# stm32.net
KiCad netlist of a schematic drawn in Altium Designer
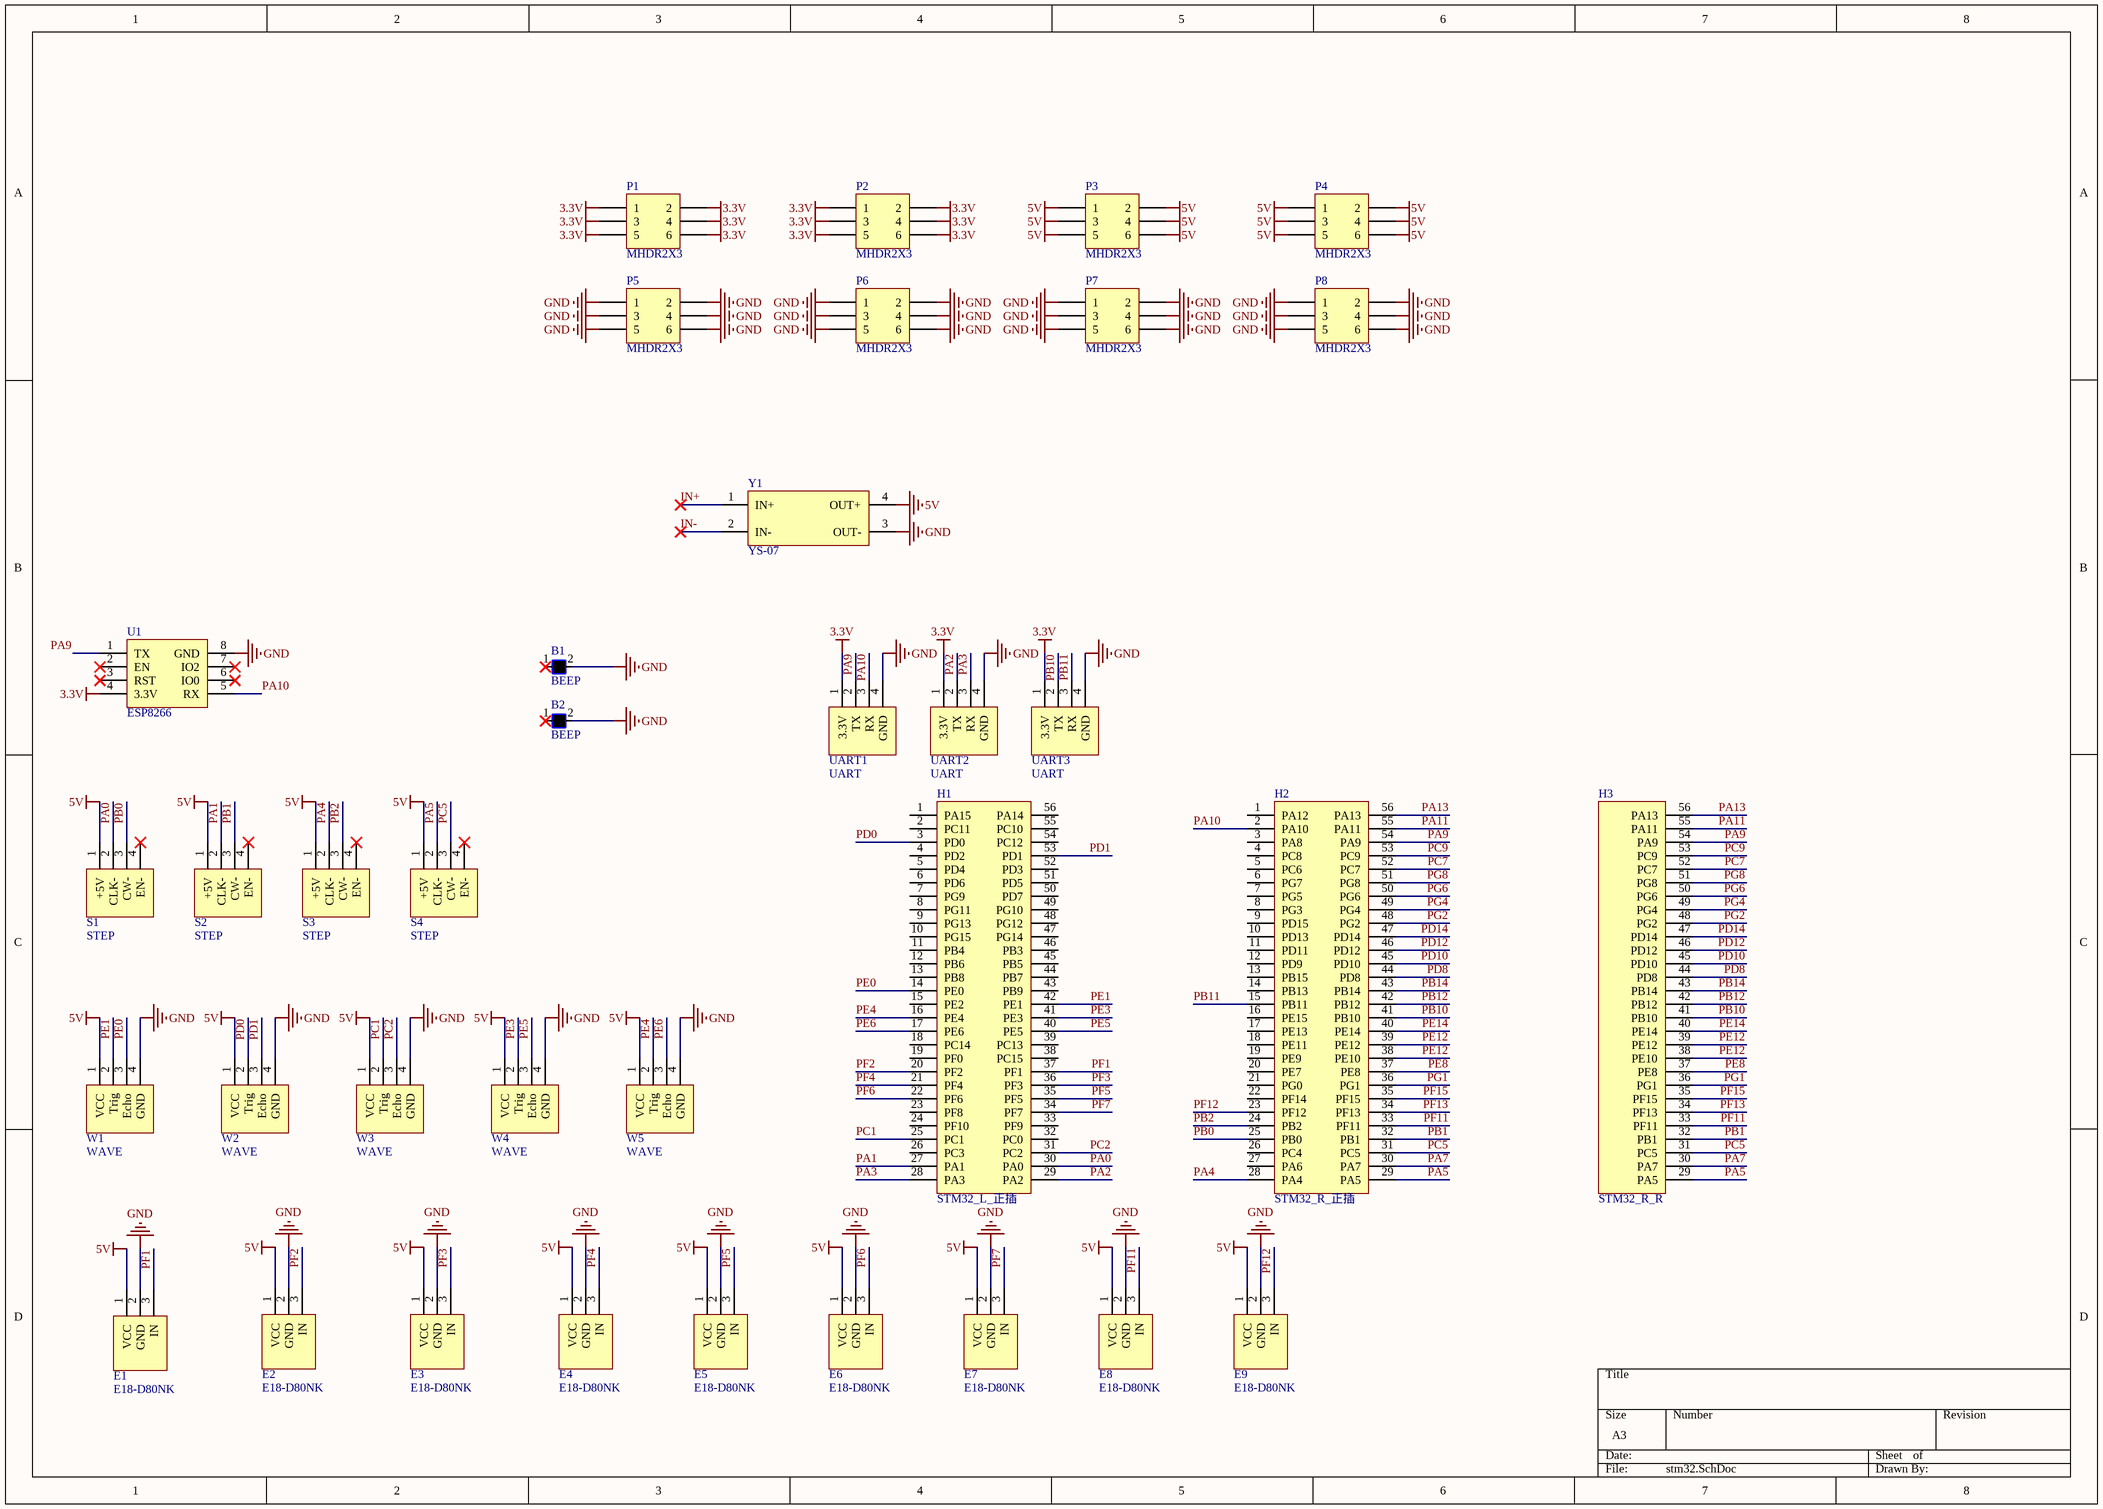
[diagram p0: stm32.SchDoc]

(export (version "E")
  (design (tool "Eeschema 10.0.6"))
  (components
    (comp (ref "B1") (value "BEEP") (footprint "BEEP") (libsource (lib "stm32") (part "BEEP")))
    (comp (ref "B2") (value "BEEP") (footprint "BEEP") (libsource (lib "stm32") (part "BEEP")))
    (comp (ref "E1") (value "E18-D80NK") (footprint "E18") (libsource (lib "stm32") (part "E18-D80NK")))
    (comp (ref "E2") (value "E18-D80NK") (footprint "E18") (libsource (lib "stm32") (part "E18-D80NK")))
    (comp (ref "E3") (value "E18-D80NK") (footprint "E18") (libsource (lib "stm32") (part "E18-D80NK")))
    (comp (ref "E4") (value "E18-D80NK") (footprint "E18") (libsource (lib "stm32") (part "E18-D80NK")))
    (comp (ref "E5") (value "E18-D80NK") (footprint "E18") (libsource (lib "stm32") (part "E18-D80NK")))
    (comp (ref "E6") (value "E18-D80NK") (footprint "E18") (libsource (lib "stm32") (part "E18-D80NK")))
    (comp (ref "E7") (value "E18-D80NK") (footprint "E18") (libsource (lib "stm32") (part "E18-D80NK")))
    (comp (ref "E8") (value "E18-D80NK") (footprint "E18") (libsource (lib "stm32") (part "E18-D80NK")))
    (comp (ref "E9") (value "E18-D80NK") (footprint "E18") (libsource (lib "stm32") (part "E18-D80NK")))
    (comp (ref "H1")
      (value "STM32_L_正插")
      (footprint "Header2*28")
      (libsource (lib "stm32") (part "STM32_L_正插"))
    )
    (comp (ref "H2")
      (value "STM32_R_正插")
      (footprint "Header2*28")
      (libsource (lib "stm32") (part "STM32_R_正插"))
    )
    (comp (ref "H3")
      (value "STM32_R_R")
      (footprint "HEADER1*28")
      (libsource (lib "stm32") (part "STM32_R_R"))
    )
    (comp (ref "P1")
      (value "MHDR2X3")
      (footprint "MHDR2X3")
      (description "Header, 3-Pin, Dual row")
      (fields (field (name "PUBLISHER") "Altium Limited"))
      (libsource (lib "Miscellaneous Connectors") (part "MHDR2X3"))
    )
    (comp (ref "P2")
      (value "MHDR2X3")
      (footprint "MHDR2X3")
      (description "Header, 3-Pin, Dual row")
      (fields (field (name "PUBLISHER") "Altium Limited"))
      (libsource (lib "Miscellaneous Connectors") (part "MHDR2X3"))
    )
    (comp (ref "P3")
      (value "MHDR2X3")
      (footprint "MHDR2X3")
      (description "Header, 3-Pin, Dual row")
      (fields (field (name "PUBLISHER") "Altium Limited"))
      (libsource (lib "Miscellaneous Connectors") (part "MHDR2X3"))
    )
    (comp (ref "P4")
      (value "MHDR2X3")
      (footprint "MHDR2X3")
      (description "Header, 3-Pin, Dual row")
      (fields (field (name "PUBLISHER") "Altium Limited"))
      (libsource (lib "Miscellaneous Connectors") (part "MHDR2X3"))
    )
    (comp (ref "P5")
      (value "MHDR2X3")
      (footprint "MHDR2X3")
      (description "Header, 3-Pin, Dual row")
      (fields (field (name "PUBLISHER") "Altium Limited"))
      (libsource (lib "Miscellaneous Connectors") (part "MHDR2X3"))
    )
    (comp (ref "P6")
      (value "MHDR2X3")
      (footprint "MHDR2X3")
      (description "Header, 3-Pin, Dual row")
      (fields (field (name "PUBLISHER") "Altium Limited"))
      (libsource (lib "Miscellaneous Connectors") (part "MHDR2X3"))
    )
    (comp (ref "P7")
      (value "MHDR2X3")
      (footprint "MHDR2X3")
      (description "Header, 3-Pin, Dual row")
      (fields (field (name "PUBLISHER") "Altium Limited"))
      (libsource (lib "Miscellaneous Connectors") (part "MHDR2X3"))
    )
    (comp (ref "P8")
      (value "MHDR2X3")
      (footprint "MHDR2X3")
      (description "Header, 3-Pin, Dual row")
      (fields (field (name "PUBLISHER") "Altium Limited"))
      (libsource (lib "Miscellaneous Connectors") (part "MHDR2X3"))
    )
    (comp (ref "S1") (value "STEP") (footprint "STEP") (libsource (lib "stm32") (part "STEP")))
    (comp (ref "S2") (value "STEP") (footprint "STEP") (libsource (lib "stm32") (part "STEP")))
    (comp (ref "S3") (value "STEP") (footprint "STEP") (libsource (lib "stm32") (part "STEP")))
    (comp (ref "S4") (value "STEP") (footprint "STEP") (libsource (lib "stm32") (part "STEP")))
    (comp (ref "U1") (value "ESP8266") (footprint "ESP8266") (libsource (lib "stm32") (part "ESP8266")))
    (comp (ref "UART1") (value "UART") (footprint "UART") (libsource (lib "stm32") (part "UART")))
    (comp (ref "UART2") (value "UART") (footprint "UART") (libsource (lib "stm32") (part "UART")))
    (comp (ref "UART3") (value "UART") (footprint "UART") (libsource (lib "stm32") (part "UART")))
    (comp (ref "W1") (value "WAVE") (footprint "WAVE1*4") (libsource (lib "stm32") (part "WAVE")))
    (comp (ref "W2") (value "WAVE") (footprint "WAVE1*4") (libsource (lib "stm32") (part "WAVE")))
    (comp (ref "W3") (value "WAVE") (footprint "WAVE1*4") (libsource (lib "stm32") (part "WAVE")))
    (comp (ref "W4") (value "WAVE") (footprint "WAVE1*4") (libsource (lib "stm32") (part "WAVE")))
    (comp (ref "W5") (value "WAVE") (footprint "WAVE1*4") (libsource (lib "stm32") (part "WAVE")))
    (comp (ref "Y1") (value "YS-07") (footprint "YS-07") (libsource (lib "stm32") (part "YS-07")))
  )
  (nets
    (net (code "1") (name "/IN+") (class "Default")
      (node (ref "Y1") (pin "1") (pinfunction "IN+_1") (pintype "passive+no_connect"))
    )
    (net (code "2") (name "/IN-") (class "Default")
      (node (ref "Y1") (pin "2") (pinfunction "IN-_2") (pintype "passive+no_connect"))
    )
    (net (code "3") (name "/PA0") (class "Default")
      (node (ref "H1") (pin "30") (pinfunction "PA0_30") (pintype "passive"))
      (node (ref "S1") (pin "2") (pinfunction "CLK-_2") (pintype "passive"))
    )
    (net (code "4") (name "/PA1") (class "Default")
      (node (ref "H1") (pin "27") (pinfunction "PA1_27") (pintype "passive"))
      (node (ref "S2") (pin "2") (pinfunction "CLK-_2") (pintype "passive"))
    )
    (net (code "5") (name "/PA2") (class "Default")
      (node (ref "H1") (pin "29") (pinfunction "PA2_29") (pintype "passive"))
      (node (ref "UART2") (pin "2") (pinfunction "TX_2") (pintype "passive"))
    )
    (net (code "6") (name "/PA3") (class "Default")
      (node (ref "H1") (pin "28") (pinfunction "PA3_28") (pintype "passive"))
      (node (ref "UART2") (pin "3") (pinfunction "RX_3") (pintype "passive"))
    )
    (net (code "7") (name "/PA4") (class "Default")
      (node (ref "H2") (pin "28") (pinfunction "PA4_28") (pintype "passive"))
      (node (ref "S3") (pin "2") (pinfunction "CLK-_2") (pintype "passive"))
    )
    (net (code "8") (name "/PA5") (class "Default")
      (node (ref "H2") (pin "29") (pinfunction "PA5_29") (pintype "passive"))
      (node (ref "H3") (pin "29") (pinfunction "PA5_29") (pintype "passive"))
      (node (ref "S4") (pin "2") (pinfunction "CLK-_2") (pintype "passive"))
    )
    (net (code "9") (name "/PA7") (class "Default")
      (node (ref "H2") (pin "30") (pinfunction "PA7_30") (pintype "passive"))
      (node (ref "H3") (pin "30") (pinfunction "PA7_30") (pintype "passive"))
    )
    (net (code "10") (name "/PA9") (class "Default")
      (node (ref "H2") (pin "54") (pinfunction "PA9_54") (pintype "passive"))
      (node (ref "H3") (pin "54") (pinfunction "PA9_54") (pintype "passive"))
      (node (ref "U1") (pin "1") (pinfunction "TX_1") (pintype "passive"))
      (node (ref "UART1") (pin "2") (pinfunction "TX_2") (pintype "passive"))
    )
    (net (code "11") (name "/PA10") (class "Default")
      (node (ref "H2") (pin "2") (pinfunction "PA10_2") (pintype "passive"))
      (node (ref "U1") (pin "5") (pinfunction "RX_5") (pintype "passive"))
      (node (ref "UART1") (pin "3") (pinfunction "RX_3") (pintype "passive"))
    )
    (net (code "12") (name "/PA11") (class "Default")
      (node (ref "H2") (pin "55") (pinfunction "PA11_55") (pintype "passive"))
      (node (ref "H3") (pin "55") (pinfunction "PA11_55") (pintype "passive"))
    )
    (net (code "13") (name "/PA13") (class "Default")
      (node (ref "H2") (pin "56") (pinfunction "PA13_56") (pintype "passive"))
      (node (ref "H3") (pin "56") (pinfunction "PA13_56") (pintype "passive"))
    )
    (net (code "14") (name "/PB0") (class "Default")
      (node (ref "H2") (pin "25") (pinfunction "PB0_25") (pintype "passive"))
      (node (ref "S1") (pin "3") (pinfunction "CW-_3") (pintype "passive"))
    )
    (net (code "15") (name "/PB1") (class "Default")
      (node (ref "H2") (pin "32") (pinfunction "PB1_32") (pintype "passive"))
      (node (ref "H3") (pin "32") (pinfunction "PB1_32") (pintype "passive"))
      (node (ref "S2") (pin "3") (pinfunction "CW-_3") (pintype "passive"))
    )
    (net (code "16") (name "/PB2") (class "Default")
      (node (ref "H2") (pin "24") (pinfunction "PB2_24") (pintype "passive"))
      (node (ref "S3") (pin "3") (pinfunction "CW-_3") (pintype "passive"))
    )
    (net (code "17") (name "/PB10") (class "Default")
      (node (ref "H2") (pin "41") (pinfunction "PB10_41") (pintype "passive"))
      (node (ref "H3") (pin "41") (pinfunction "PB10_41") (pintype "passive"))
      (node (ref "UART3") (pin "2") (pinfunction "TX_2") (pintype "passive"))
    )
    (net (code "18") (name "/PB11") (class "Default")
      (node (ref "H2") (pin "15") (pinfunction "PB11_15") (pintype "passive"))
      (node (ref "UART3") (pin "3") (pinfunction "RX_3") (pintype "passive"))
    )
    (net (code "19") (name "/PB12") (class "Default")
      (node (ref "H2") (pin "42") (pinfunction "PB12_42") (pintype "passive"))
      (node (ref "H3") (pin "42") (pinfunction "PB12_42") (pintype "passive"))
    )
    (net (code "20") (name "/PB14") (class "Default")
      (node (ref "H2") (pin "43") (pinfunction "PB14_43") (pintype "passive"))
      (node (ref "H3") (pin "43") (pinfunction "PB14_43") (pintype "passive"))
    )
    (net (code "21") (name "/PC1") (class "Default")
      (node (ref "H1") (pin "25") (pinfunction "PC1_25") (pintype "passive"))
      (node (ref "W3") (pin "2") (pinfunction "Trig_2") (pintype "passive"))
    )
    (net (code "22") (name "/PC2") (class "Default")
      (node (ref "H1") (pin "31") (pinfunction "PC2_31") (pintype "passive"))
      (node (ref "W3") (pin "3") (pinfunction "Echo_3") (pintype "passive"))
    )
    (net (code "23") (name "/PC5") (class "Default")
      (node (ref "H2") (pin "31") (pinfunction "PC5_31") (pintype "passive"))
      (node (ref "H3") (pin "31") (pinfunction "PC5_31") (pintype "passive"))
      (node (ref "S4") (pin "3") (pinfunction "CW-_3") (pintype "passive"))
    )
    (net (code "24") (name "/PC7") (class "Default")
      (node (ref "H2") (pin "52") (pinfunction "PC7_52") (pintype "passive"))
      (node (ref "H3") (pin "52") (pinfunction "PC7_52") (pintype "passive"))
    )
    (net (code "25") (name "/PC9") (class "Default")
      (node (ref "H2") (pin "53") (pinfunction "PC9_53") (pintype "passive"))
      (node (ref "H3") (pin "53") (pinfunction "PC9_53") (pintype "passive"))
    )
    (net (code "26") (name "/PD0") (class "Default")
      (node (ref "H1") (pin "3") (pinfunction "PD0_3") (pintype "passive"))
      (node (ref "W2") (pin "2") (pinfunction "Trig_2") (pintype "passive"))
    )
    (net (code "27") (name "/PD1") (class "Default")
      (node (ref "H1") (pin "53") (pinfunction "PD1_53") (pintype "passive"))
      (node (ref "W2") (pin "3") (pinfunction "Echo_3") (pintype "passive"))
    )
    (net (code "28") (name "/PD8") (class "Default")
      (node (ref "H2") (pin "44") (pinfunction "PD8_44") (pintype "passive"))
      (node (ref "H3") (pin "44") (pinfunction "PD8_44") (pintype "passive"))
    )
    (net (code "29") (name "/PD10") (class "Default")
      (node (ref "H2") (pin "45") (pinfunction "PD10_45") (pintype "passive"))
      (node (ref "H3") (pin "45") (pinfunction "PD10_45") (pintype "passive"))
    )
    (net (code "30") (name "/PD12") (class "Default")
      (node (ref "H2") (pin "46") (pinfunction "PD12_46") (pintype "passive"))
      (node (ref "H3") (pin "46") (pinfunction "PD12_46") (pintype "passive"))
    )
    (net (code "31") (name "/PD14") (class "Default")
      (node (ref "H2") (pin "47") (pinfunction "PD14_47") (pintype "passive"))
      (node (ref "H3") (pin "47") (pinfunction "PD14_47") (pintype "passive"))
    )
    (net (code "32") (name "/PE0") (class "Default")
      (node (ref "H1") (pin "14") (pinfunction "PE0_14") (pintype "passive"))
      (node (ref "W1") (pin "3") (pinfunction "Echo_3") (pintype "passive"))
    )
    (net (code "33") (name "/PE1") (class "Default")
      (node (ref "H1") (pin "42") (pinfunction "PE1_42") (pintype "passive"))
      (node (ref "W1") (pin "2") (pinfunction "Trig_2") (pintype "passive"))
    )
    (net (code "34") (name "/PE3") (class "Default")
      (node (ref "H1") (pin "41") (pinfunction "PE3_41") (pintype "passive"))
      (node (ref "W4") (pin "2") (pinfunction "Trig_2") (pintype "passive"))
    )
    (net (code "35") (name "/PE4") (class "Default")
      (node (ref "H1") (pin "16") (pinfunction "PE4_16") (pintype "passive"))
      (node (ref "W5") (pin "2") (pinfunction "Trig_2") (pintype "passive"))
    )
    (net (code "36") (name "/PE5") (class "Default")
      (node (ref "H1") (pin "40") (pinfunction "PE5_40") (pintype "passive"))
      (node (ref "W4") (pin "3") (pinfunction "Echo_3") (pintype "passive"))
    )
    (net (code "37") (name "/PE6") (class "Default")
      (node (ref "H1") (pin "17") (pinfunction "PE6_17") (pintype "passive"))
      (node (ref "W5") (pin "3") (pinfunction "Echo_3") (pintype "passive"))
    )
    (net (code "38") (name "/PE8") (class "Default")
      (node (ref "H2") (pin "37") (pinfunction "PE8_37") (pintype "passive"))
      (node (ref "H3") (pin "37") (pinfunction "PE8_37") (pintype "passive"))
    )
    (net (code "39") (name "/PE12") (class "Default")
      (node (ref "H2") (pin "38") (pinfunction "PE10_38") (pintype "passive"))
      (node (ref "H2") (pin "39") (pinfunction "PE12_39") (pintype "passive"))
      (node (ref "H3") (pin "38") (pinfunction "PE10_38") (pintype "passive"))
      (node (ref "H3") (pin "39") (pinfunction "PE12_39") (pintype "passive"))
    )
    (net (code "40") (name "/PE14") (class "Default")
      (node (ref "H2") (pin "40") (pinfunction "PE14_40") (pintype "passive"))
      (node (ref "H3") (pin "40") (pinfunction "PE14_40") (pintype "passive"))
    )
    (net (code "41") (name "/PF1") (class "Default")
      (node (ref "E1") (pin "3") (pinfunction "IN_3") (pintype "passive"))
      (node (ref "H1") (pin "37") (pinfunction "PF1_37") (pintype "passive"))
    )
    (net (code "42") (name "/PF2") (class "Default")
      (node (ref "E2") (pin "3") (pinfunction "IN_3") (pintype "passive"))
      (node (ref "H1") (pin "20") (pinfunction "PF2_20") (pintype "passive"))
    )
    (net (code "43") (name "/PF3") (class "Default")
      (node (ref "E3") (pin "3") (pinfunction "IN_3") (pintype "passive"))
      (node (ref "H1") (pin "36") (pinfunction "PF3_36") (pintype "passive"))
    )
    (net (code "44") (name "/PF4") (class "Default")
      (node (ref "E4") (pin "3") (pinfunction "IN_3") (pintype "passive"))
      (node (ref "H1") (pin "21") (pinfunction "PF4_21") (pintype "passive"))
    )
    (net (code "45") (name "/PF5") (class "Default")
      (node (ref "E5") (pin "3") (pinfunction "IN_3") (pintype "passive"))
      (node (ref "H1") (pin "35") (pinfunction "PF5_35") (pintype "passive"))
    )
    (net (code "46") (name "/PF6") (class "Default")
      (node (ref "E6") (pin "3") (pinfunction "IN_3") (pintype "passive"))
      (node (ref "H1") (pin "22") (pinfunction "PF6_22") (pintype "passive"))
    )
    (net (code "47") (name "/PF7") (class "Default")
      (node (ref "E7") (pin "3") (pinfunction "IN_3") (pintype "passive"))
      (node (ref "H1") (pin "34") (pinfunction "PF7_34") (pintype "passive"))
    )
    (net (code "48") (name "/PF11") (class "Default")
      (node (ref "E8") (pin "3") (pinfunction "IN_3") (pintype "passive"))
      (node (ref "H2") (pin "33") (pinfunction "PF11_33") (pintype "passive"))
      (node (ref "H3") (pin "33") (pinfunction "PF11_33") (pintype "passive"))
    )
    (net (code "49") (name "/PF12") (class "Default")
      (node (ref "E9") (pin "3") (pinfunction "IN_3") (pintype "passive"))
      (node (ref "H2") (pin "23") (pinfunction "PF12_23") (pintype "passive"))
    )
    (net (code "50") (name "/PF13") (class "Default")
      (node (ref "H2") (pin "34") (pinfunction "PF13_34") (pintype "passive"))
      (node (ref "H3") (pin "34") (pinfunction "PF13_34") (pintype "passive"))
    )
    (net (code "51") (name "/PF15") (class "Default")
      (node (ref "H2") (pin "35") (pinfunction "PF15_35") (pintype "passive"))
      (node (ref "H3") (pin "35") (pinfunction "PF15_35") (pintype "passive"))
    )
    (net (code "52") (name "/PG1") (class "Default")
      (node (ref "H2") (pin "36") (pinfunction "PG1_36") (pintype "passive"))
      (node (ref "H3") (pin "36") (pinfunction "PG1_36") (pintype "passive"))
    )
    (net (code "53") (name "/PG2") (class "Default")
      (node (ref "H2") (pin "48") (pinfunction "PG2_48") (pintype "passive"))
      (node (ref "H3") (pin "48") (pinfunction "PG2_48") (pintype "passive"))
    )
    (net (code "54") (name "/PG4") (class "Default")
      (node (ref "H2") (pin "49") (pinfunction "PG4_49") (pintype "passive"))
      (node (ref "H3") (pin "49") (pinfunction "PG4_49") (pintype "passive"))
    )
    (net (code "55") (name "/PG6") (class "Default")
      (node (ref "H2") (pin "50") (pinfunction "PG6_50") (pintype "passive"))
      (node (ref "H3") (pin "50") (pinfunction "PG6_50") (pintype "passive"))
    )
    (net (code "56") (name "/PG8") (class "Default")
      (node (ref "H2") (pin "51") (pinfunction "PG8_51") (pintype "passive"))
      (node (ref "H3") (pin "51") (pinfunction "PG8_51") (pintype "passive"))
    )
    (net (code "57") (name "3.3V") (class "Default")
      (node (ref "P1") (pin "1") (pinfunction "1_1") (pintype "passive"))
      (node (ref "P1") (pin "2") (pinfunction "2_2") (pintype "passive"))
      (node (ref "P1") (pin "3") (pinfunction "3_3") (pintype "passive"))
      (node (ref "P1") (pin "4") (pinfunction "4_4") (pintype "passive"))
      (node (ref "P1") (pin "5") (pinfunction "5_5") (pintype "passive"))
      (node (ref "P1") (pin "6") (pinfunction "6_6") (pintype "passive"))
      (node (ref "P2") (pin "1") (pinfunction "1_1") (pintype "passive"))
      (node (ref "P2") (pin "2") (pinfunction "2_2") (pintype "passive"))
      (node (ref "P2") (pin "3") (pinfunction "3_3") (pintype "passive"))
      (node (ref "P2") (pin "4") (pinfunction "4_4") (pintype "passive"))
      (node (ref "P2") (pin "5") (pinfunction "5_5") (pintype "passive"))
      (node (ref "P2") (pin "6") (pinfunction "6_6") (pintype "passive"))
      (node (ref "U1") (pin "4") (pinfunction "3.3V_4") (pintype "passive"))
      (node (ref "UART1") (pin "1") (pinfunction "3.3V_1") (pintype "passive"))
      (node (ref "UART2") (pin "1") (pinfunction "3.3V_1") (pintype "passive"))
      (node (ref "UART3") (pin "1") (pinfunction "3.3V_1") (pintype "passive"))
    )
    (net (code "58") (name "5V") (class "Default")
      (node (ref "E1") (pin "1") (pinfunction "VCC_1") (pintype "passive"))
      (node (ref "E2") (pin "1") (pinfunction "VCC_1") (pintype "passive"))
      (node (ref "E3") (pin "1") (pinfunction "VCC_1") (pintype "passive"))
      (node (ref "E4") (pin "1") (pinfunction "VCC_1") (pintype "passive"))
      (node (ref "E5") (pin "1") (pinfunction "VCC_1") (pintype "passive"))
      (node (ref "E6") (pin "1") (pinfunction "VCC_1") (pintype "passive"))
      (node (ref "E7") (pin "1") (pinfunction "VCC_1") (pintype "passive"))
      (node (ref "E8") (pin "1") (pinfunction "VCC_1") (pintype "passive"))
      (node (ref "E9") (pin "1") (pinfunction "VCC_1") (pintype "passive"))
      (node (ref "P3") (pin "1") (pinfunction "1_1") (pintype "passive"))
      (node (ref "P3") (pin "2") (pinfunction "2_2") (pintype "passive"))
      (node (ref "P3") (pin "3") (pinfunction "3_3") (pintype "passive"))
      (node (ref "P3") (pin "4") (pinfunction "4_4") (pintype "passive"))
      (node (ref "P3") (pin "5") (pinfunction "5_5") (pintype "passive"))
      (node (ref "P3") (pin "6") (pinfunction "6_6") (pintype "passive"))
      (node (ref "P4") (pin "1") (pinfunction "1_1") (pintype "passive"))
      (node (ref "P4") (pin "2") (pinfunction "2_2") (pintype "passive"))
      (node (ref "P4") (pin "3") (pinfunction "3_3") (pintype "passive"))
      (node (ref "P4") (pin "4") (pinfunction "4_4") (pintype "passive"))
      (node (ref "P4") (pin "5") (pinfunction "5_5") (pintype "passive"))
      (node (ref "P4") (pin "6") (pinfunction "6_6") (pintype "passive"))
      (node (ref "S1") (pin "1") (pinfunction "+5V_1") (pintype "passive"))
      (node (ref "S2") (pin "1") (pinfunction "+5V_1") (pintype "passive"))
      (node (ref "S3") (pin "1") (pinfunction "+5V_1") (pintype "passive"))
      (node (ref "S4") (pin "1") (pinfunction "+5V_1") (pintype "passive"))
      (node (ref "W1") (pin "1") (pinfunction "VCC_1") (pintype "passive"))
      (node (ref "W2") (pin "1") (pinfunction "VCC_1") (pintype "passive"))
      (node (ref "W3") (pin "1") (pinfunction "VCC_1") (pintype "passive"))
      (node (ref "W4") (pin "1") (pinfunction "VCC_1") (pintype "passive"))
      (node (ref "W5") (pin "1") (pinfunction "VCC_1") (pintype "passive"))
      (node (ref "Y1") (pin "4") (pinfunction "OUT+_4") (pintype "passive"))
    )
    (net (code "59") (name "GND") (class "Default")
      (node (ref "B1") (pin "2") (pinfunction "GND_2") (pintype "passive"))
      (node (ref "B2") (pin "2") (pinfunction "GND_2") (pintype "passive"))
      (node (ref "E1") (pin "2") (pinfunction "GND_2") (pintype "passive"))
      (node (ref "E2") (pin "2") (pinfunction "GND_2") (pintype "passive"))
      (node (ref "E3") (pin "2") (pinfunction "GND_2") (pintype "passive"))
      (node (ref "E4") (pin "2") (pinfunction "GND_2") (pintype "passive"))
      (node (ref "E5") (pin "2") (pinfunction "GND_2") (pintype "passive"))
      (node (ref "E6") (pin "2") (pinfunction "GND_2") (pintype "passive"))
      (node (ref "E7") (pin "2") (pinfunction "GND_2") (pintype "passive"))
      (node (ref "E8") (pin "2") (pinfunction "GND_2") (pintype "passive"))
      (node (ref "E9") (pin "2") (pinfunction "GND_2") (pintype "passive"))
      (node (ref "P5") (pin "1") (pinfunction "1_1") (pintype "passive"))
      (node (ref "P5") (pin "2") (pinfunction "2_2") (pintype "passive"))
      (node (ref "P5") (pin "3") (pinfunction "3_3") (pintype "passive"))
      (node (ref "P5") (pin "4") (pinfunction "4_4") (pintype "passive"))
      (node (ref "P5") (pin "5") (pinfunction "5_5") (pintype "passive"))
      (node (ref "P5") (pin "6") (pinfunction "6_6") (pintype "passive"))
      (node (ref "P6") (pin "1") (pinfunction "1_1") (pintype "passive"))
      (node (ref "P6") (pin "2") (pinfunction "2_2") (pintype "passive"))
      (node (ref "P6") (pin "3") (pinfunction "3_3") (pintype "passive"))
      (node (ref "P6") (pin "4") (pinfunction "4_4") (pintype "passive"))
      (node (ref "P6") (pin "5") (pinfunction "5_5") (pintype "passive"))
      (node (ref "P6") (pin "6") (pinfunction "6_6") (pintype "passive"))
      (node (ref "P7") (pin "1") (pinfunction "1_1") (pintype "passive"))
      (node (ref "P7") (pin "2") (pinfunction "2_2") (pintype "passive"))
      (node (ref "P7") (pin "3") (pinfunction "3_3") (pintype "passive"))
      (node (ref "P7") (pin "4") (pinfunction "4_4") (pintype "passive"))
      (node (ref "P7") (pin "5") (pinfunction "5_5") (pintype "passive"))
      (node (ref "P7") (pin "6") (pinfunction "6_6") (pintype "passive"))
      (node (ref "P8") (pin "1") (pinfunction "1_1") (pintype "passive"))
      (node (ref "P8") (pin "2") (pinfunction "2_2") (pintype "passive"))
      (node (ref "P8") (pin "3") (pinfunction "3_3") (pintype "passive"))
      (node (ref "P8") (pin "4") (pinfunction "4_4") (pintype "passive"))
      (node (ref "P8") (pin "5") (pinfunction "5_5") (pintype "passive"))
      (node (ref "P8") (pin "6") (pinfunction "6_6") (pintype "passive"))
      (node (ref "U1") (pin "8") (pinfunction "GND_8") (pintype "passive"))
      (node (ref "UART1") (pin "4") (pinfunction "GND_4") (pintype "passive"))
      (node (ref "UART2") (pin "4") (pinfunction "GND_4") (pintype "passive"))
      (node (ref "UART3") (pin "4") (pinfunction "GND_4") (pintype "passive"))
      (node (ref "W1") (pin "4") (pinfunction "GND_4") (pintype "passive"))
      (node (ref "W2") (pin "4") (pinfunction "GND_4") (pintype "passive"))
      (node (ref "W3") (pin "4") (pinfunction "GND_4") (pintype "passive"))
      (node (ref "W4") (pin "4") (pinfunction "GND_4") (pintype "passive"))
      (node (ref "W5") (pin "4") (pinfunction "GND_4") (pintype "passive"))
      (node (ref "Y1") (pin "3") (pinfunction "OUT-_3") (pintype "passive"))
    )
    (net (code "60") (name "unconnected-(B1-IN-Pad1)") (class "Default")
      (node (ref "B1") (pin "1") (pinfunction "IN_1") (pintype "passive+no_connect"))
    )
    (net (code "61") (name "unconnected-(B2-IN-Pad1)") (class "Default")
      (node (ref "B2") (pin "1") (pinfunction "IN_1") (pintype "passive+no_connect"))
    )
    (net (code "62") (name "unconnected-(H1-PA14-Pad56)") (class "Default")
      (node (ref "H1") (pin "56") (pinfunction "PA14_56") (pintype "passive"))
    )
    (net (code "63") (name "unconnected-(H1-PA15-Pad1)") (class "Default")
      (node (ref "H1") (pin "1") (pinfunction "PA15_1") (pintype "passive"))
    )
    (net (code "64") (name "unconnected-(H1-PB3-Pad46)") (class "Default")
      (node (ref "H1") (pin "46") (pinfunction "PB3_46") (pintype "passive"))
    )
    (net (code "65") (name "unconnected-(H1-PB4-Pad11)") (class "Default")
      (node (ref "H1") (pin "11") (pinfunction "PB4_11") (pintype "passive"))
    )
    (net (code "66") (name "unconnected-(H1-PB5-Pad45)") (class "Default")
      (node (ref "H1") (pin "45") (pinfunction "PB5_45") (pintype "passive"))
    )
    (net (code "67") (name "unconnected-(H1-PB6-Pad12)") (class "Default")
      (node (ref "H1") (pin "12") (pinfunction "PB6_12") (pintype "passive"))
    )
    (net (code "68") (name "unconnected-(H1-PB7-Pad44)") (class "Default")
      (node (ref "H1") (pin "44") (pinfunction "PB7_44") (pintype "passive"))
    )
    (net (code "69") (name "unconnected-(H1-PB8-Pad13)") (class "Default")
      (node (ref "H1") (pin "13") (pinfunction "PB8_13") (pintype "passive"))
    )
    (net (code "70") (name "unconnected-(H1-PB9-Pad43)") (class "Default")
      (node (ref "H1") (pin "43") (pinfunction "PB9_43") (pintype "passive"))
    )
    (net (code "71") (name "unconnected-(H1-PC0-Pad32)") (class "Default")
      (node (ref "H1") (pin "32") (pinfunction "PC0_32") (pintype "passive"))
    )
    (net (code "72") (name "unconnected-(H1-PC3-Pad26)") (class "Default")
      (node (ref "H1") (pin "26") (pinfunction "PC3_26") (pintype "passive"))
    )
    (net (code "73") (name "unconnected-(H1-PC10-Pad55)") (class "Default")
      (node (ref "H1") (pin "55") (pinfunction "PC10_55") (pintype "passive"))
    )
    (net (code "74") (name "unconnected-(H1-PC11-Pad2)") (class "Default")
      (node (ref "H1") (pin "2") (pinfunction "PC11_2") (pintype "passive"))
    )
    (net (code "75") (name "unconnected-(H1-PC12-Pad54)") (class "Default")
      (node (ref "H1") (pin "54") (pinfunction "PC12_54") (pintype "passive"))
    )
    (net (code "76") (name "unconnected-(H1-PC13-Pad39)") (class "Default")
      (node (ref "H1") (pin "39") (pinfunction "PC13_39") (pintype "passive"))
    )
    (net (code "77") (name "unconnected-(H1-PC14-Pad18)") (class "Default")
      (node (ref "H1") (pin "18") (pinfunction "PC14_18") (pintype "passive"))
    )
    (net (code "78") (name "unconnected-(H1-PC15-Pad38)") (class "Default")
      (node (ref "H1") (pin "38") (pinfunction "PC15_38") (pintype "passive"))
    )
    (net (code "79") (name "unconnected-(H1-PD2-Pad4)") (class "Default")
      (node (ref "H1") (pin "4") (pinfunction "PD2_4") (pintype "passive"))
    )
    (net (code "80") (name "unconnected-(H1-PD3-Pad52)") (class "Default")
      (node (ref "H1") (pin "52") (pinfunction "PD3_52") (pintype "passive"))
    )
    (net (code "81") (name "unconnected-(H1-PD4-Pad5)") (class "Default")
      (node (ref "H1") (pin "5") (pinfunction "PD4_5") (pintype "passive"))
    )
    (net (code "82") (name "unconnected-(H1-PD5-Pad51)") (class "Default")
      (node (ref "H1") (pin "51") (pinfunction "PD5_51") (pintype "passive"))
    )
    (net (code "83") (name "unconnected-(H1-PD6-Pad6)") (class "Default")
      (node (ref "H1") (pin "6") (pinfunction "PD6_6") (pintype "passive"))
    )
    (net (code "84") (name "unconnected-(H1-PD7-Pad50)") (class "Default")
      (node (ref "H1") (pin "50") (pinfunction "PD7_50") (pintype "passive"))
    )
    (net (code "85") (name "unconnected-(H1-PE2-Pad15)") (class "Default")
      (node (ref "H1") (pin "15") (pinfunction "PE2_15") (pintype "passive"))
    )
    (net (code "86") (name "unconnected-(H1-PF0-Pad19)") (class "Default")
      (node (ref "H1") (pin "19") (pinfunction "PF0_19") (pintype "passive"))
    )
    (net (code "87") (name "unconnected-(H1-PF8-Pad23)") (class "Default")
      (node (ref "H1") (pin "23") (pinfunction "PF8_23") (pintype "passive"))
    )
    (net (code "88") (name "unconnected-(H1-PF9-Pad33)") (class "Default")
      (node (ref "H1") (pin "33") (pinfunction "PF9_33") (pintype "passive"))
    )
    (net (code "89") (name "unconnected-(H1-PF10-Pad24)") (class "Default")
      (node (ref "H1") (pin "24") (pinfunction "PF10_24") (pintype "passive"))
    )
    (net (code "90") (name "unconnected-(H1-PG9-Pad7)") (class "Default")
      (node (ref "H1") (pin "7") (pinfunction "PG9_7") (pintype "passive"))
    )
    (net (code "91") (name "unconnected-(H1-PG10-Pad49)") (class "Default")
      (node (ref "H1") (pin "49") (pinfunction "PG10_49") (pintype "passive"))
    )
    (net (code "92") (name "unconnected-(H1-PG11-Pad8)") (class "Default")
      (node (ref "H1") (pin "8") (pinfunction "PG11_8") (pintype "passive"))
    )
    (net (code "93") (name "unconnected-(H1-PG12-Pad48)") (class "Default")
      (node (ref "H1") (pin "48") (pinfunction "PG12_48") (pintype "passive"))
    )
    (net (code "94") (name "unconnected-(H1-PG13-Pad9)") (class "Default")
      (node (ref "H1") (pin "9") (pinfunction "PG13_9") (pintype "passive"))
    )
    (net (code "95") (name "unconnected-(H1-PG14-Pad47)") (class "Default")
      (node (ref "H1") (pin "47") (pinfunction "PG14_47") (pintype "passive"))
    )
    (net (code "96") (name "unconnected-(H1-PG15-Pad10)") (class "Default")
      (node (ref "H1") (pin "10") (pinfunction "PG15_10") (pintype "passive"))
    )
    (net (code "97") (name "unconnected-(H2-PA6-Pad27)") (class "Default")
      (node (ref "H2") (pin "27") (pinfunction "PA6_27") (pintype "passive"))
    )
    (net (code "98") (name "unconnected-(H2-PA8-Pad3)") (class "Default")
      (node (ref "H2") (pin "3") (pinfunction "PA8_3") (pintype "passive"))
    )
    (net (code "99") (name "unconnected-(H2-PA12-Pad1)") (class "Default")
      (node (ref "H2") (pin "1") (pinfunction "PA12_1") (pintype "passive"))
    )
    (net (code "100") (name "unconnected-(H2-PB13-Pad14)") (class "Default")
      (node (ref "H2") (pin "14") (pinfunction "PB13_14") (pintype "passive"))
    )
    (net (code "101") (name "unconnected-(H2-PB15-Pad13)") (class "Default")
      (node (ref "H2") (pin "13") (pinfunction "PB15_13") (pintype "passive"))
    )
    (net (code "102") (name "unconnected-(H2-PC4-Pad26)") (class "Default")
      (node (ref "H2") (pin "26") (pinfunction "PC4_26") (pintype "passive"))
    )
    (net (code "103") (name "unconnected-(H2-PC6-Pad5)") (class "Default")
      (node (ref "H2") (pin "5") (pinfunction "PC6_5") (pintype "passive"))
    )
    (net (code "104") (name "unconnected-(H2-PC8-Pad4)") (class "Default")
      (node (ref "H2") (pin "4") (pinfunction "PC8_4") (pintype "passive"))
    )
    (net (code "105") (name "unconnected-(H2-PD9-Pad12)") (class "Default")
      (node (ref "H2") (pin "12") (pinfunction "PD9_12") (pintype "passive"))
    )
    (net (code "106") (name "unconnected-(H2-PD11-Pad11)") (class "Default")
      (node (ref "H2") (pin "11") (pinfunction "PD11_11") (pintype "passive"))
    )
    (net (code "107") (name "unconnected-(H2-PD13-Pad10)") (class "Default")
      (node (ref "H2") (pin "10") (pinfunction "PD13_10") (pintype "passive"))
    )
    (net (code "108") (name "unconnected-(H2-PD15-Pad9)") (class "Default")
      (node (ref "H2") (pin "9") (pinfunction "PD15_9") (pintype "passive"))
    )
    (net (code "109") (name "unconnected-(H2-PE7-Pad20)") (class "Default")
      (node (ref "H2") (pin "20") (pinfunction "PE7_20") (pintype "passive"))
    )
    (net (code "110") (name "unconnected-(H2-PE9-Pad19)") (class "Default")
      (node (ref "H2") (pin "19") (pinfunction "PE9_19") (pintype "passive"))
    )
    (net (code "111") (name "unconnected-(H2-PE11-Pad18)") (class "Default")
      (node (ref "H2") (pin "18") (pinfunction "PE11_18") (pintype "passive"))
    )
    (net (code "112") (name "unconnected-(H2-PE13-Pad17)") (class "Default")
      (node (ref "H2") (pin "17") (pinfunction "PE13_17") (pintype "passive"))
    )
    (net (code "113") (name "unconnected-(H2-PE15-Pad16)") (class "Default")
      (node (ref "H2") (pin "16") (pinfunction "PE15_16") (pintype "passive"))
    )
    (net (code "114") (name "unconnected-(H2-PF14-Pad22)") (class "Default")
      (node (ref "H2") (pin "22") (pinfunction "PF14_22") (pintype "passive"))
    )
    (net (code "115") (name "unconnected-(H2-PG0-Pad21)") (class "Default")
      (node (ref "H2") (pin "21") (pinfunction "PG0_21") (pintype "passive"))
    )
    (net (code "116") (name "unconnected-(H2-PG3-Pad8)") (class "Default")
      (node (ref "H2") (pin "8") (pinfunction "PG3_8") (pintype "passive"))
    )
    (net (code "117") (name "unconnected-(H2-PG5-Pad7)") (class "Default")
      (node (ref "H2") (pin "7") (pinfunction "PG5_7") (pintype "passive"))
    )
    (net (code "118") (name "unconnected-(H2-PG7-Pad6)") (class "Default")
      (node (ref "H2") (pin "6") (pinfunction "PG7_6") (pintype "passive"))
    )
    (net (code "119") (name "unconnected-(S1-EN--Pad4)") (class "Default")
      (node (ref "S1") (pin "4") (pinfunction "EN-_4") (pintype "passive+no_connect"))
    )
    (net (code "120") (name "unconnected-(S2-EN--Pad4)") (class "Default")
      (node (ref "S2") (pin "4") (pinfunction "EN-_4") (pintype "passive+no_connect"))
    )
    (net (code "121") (name "unconnected-(S3-EN--Pad4)") (class "Default")
      (node (ref "S3") (pin "4") (pinfunction "EN-_4") (pintype "passive+no_connect"))
    )
    (net (code "122") (name "unconnected-(S4-EN--Pad4)") (class "Default")
      (node (ref "S4") (pin "4") (pinfunction "EN-_4") (pintype "passive+no_connect"))
    )
    (net (code "123") (name "unconnected-(U1-EN-Pad2)") (class "Default")
      (node (ref "U1") (pin "2") (pinfunction "EN_2") (pintype "passive+no_connect"))
    )
    (net (code "124") (name "unconnected-(U1-IO0-Pad6)") (class "Default")
      (node (ref "U1") (pin "6") (pinfunction "IO0_6") (pintype "passive+no_connect"))
    )
    (net (code "125") (name "unconnected-(U1-IO2-Pad7)") (class "Default")
      (node (ref "U1") (pin "7") (pinfunction "IO2_7") (pintype "passive+no_connect"))
    )
    (net (code "126") (name "unconnected-(U1-RST-Pad3)") (class "Default")
      (node (ref "U1") (pin "3") (pinfunction "RST_3") (pintype "passive+no_connect"))
    )
  )
)
